# Sheet1.net
KiCad netlist of a schematic drawn in Altium Designer
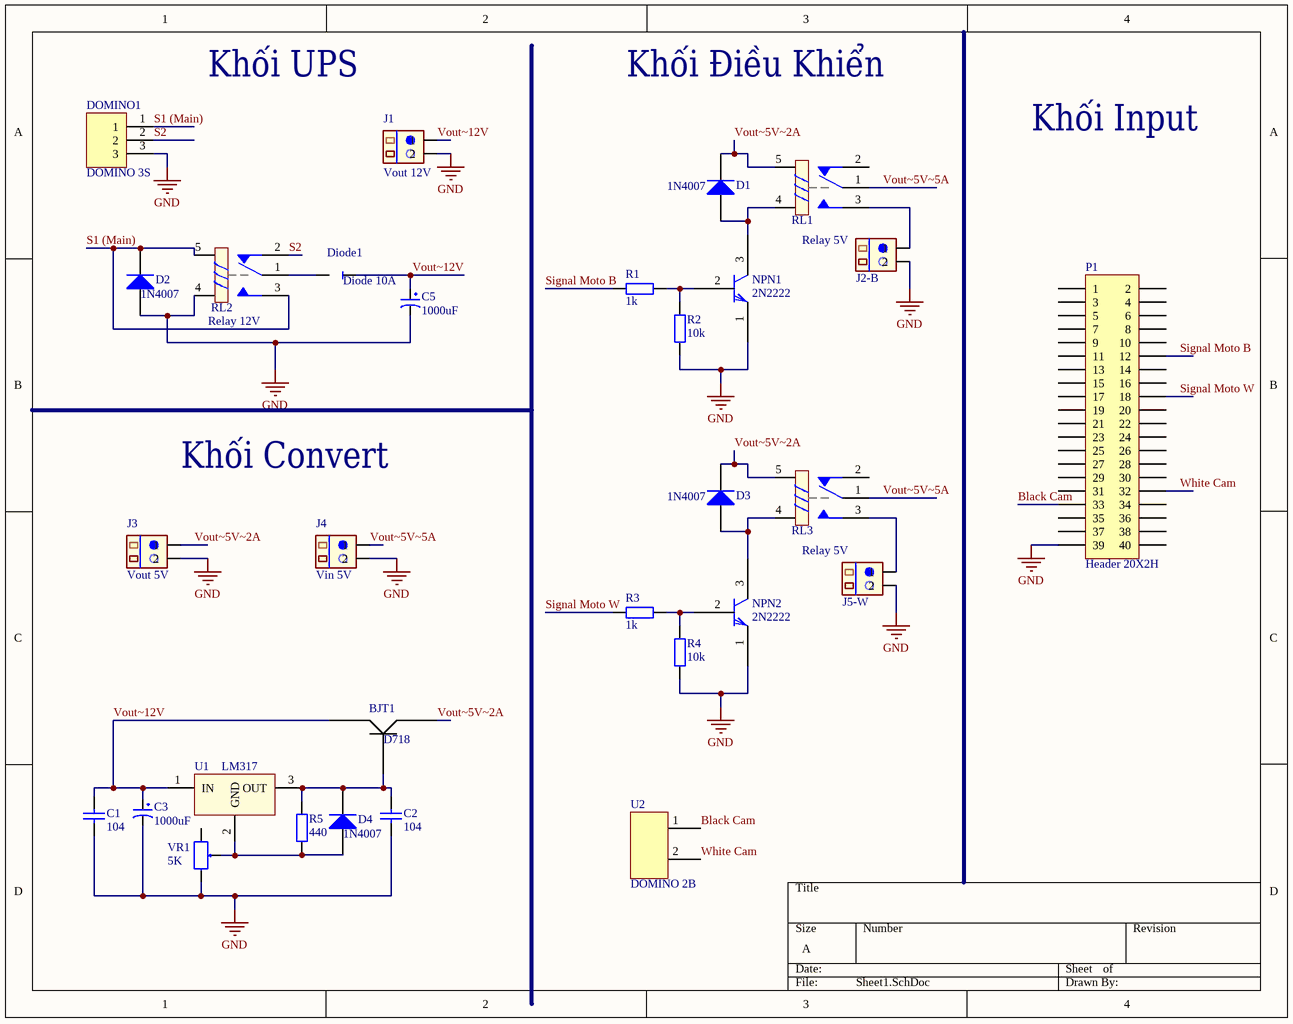
[diagram p0: Sheet1.SchDoc]

(export (version "E")
  (design (tool "Eeschema 10.0.6"))
  (components
    (comp (ref "BJT1") (value "D718") (footprint "2sb688") (libsource (lib "2sb688") (part "BJT 2sb688")))
    (comp (ref "C1")
      (value "104")
      (footprint "tu gom")
      (description "Cắm")
      (libsource (lib "THU VIEN SCH") (part "Tu gom 104 50V"))
    )
    (comp (ref "C2")
      (value "104")
      (footprint "tu gom")
      (description "Cắm")
      (libsource (lib "THU VIEN SCH") (part "Tu gom 104 50V"))
    )
    (comp (ref "C3")
      (value "1000uF")
      (footprint "tu hoa 13mm")
      (description "Cắm")
      (libsource (lib "THU VIEN SCH") (part "Tu Hoa 1000uF 25V 13x21"))
    )
    (comp (ref "C5")
      (value "1000uF")
      (footprint "tu hoa 13mm")
      (description "Cắm")
      (libsource (lib "THU VIEN SCH") (part "Tu Hoa 1000uF 25V 13x21"))
    )
    (comp (ref "D1")
      (value "1N4007")
      (footprint "DO-41")
      (description "1 Amp General Purpose Rectifier")
      (fields (field (name "PUBLISHER") "Altium Limited"))
      (libsource (lib "hphonglib") (part "Diode 1N4007"))
    )
    (comp (ref "D2")
      (value "1N4007")
      (footprint "DO-41")
      (description "1 Amp General Purpose Rectifier")
      (fields (field (name "PUBLISHER") "Altium Limited"))
      (libsource (lib "hphonglib") (part "Diode 1N4007"))
    )
    (comp (ref "D3")
      (value "1N4007")
      (footprint "DO-41")
      (description "1 Amp General Purpose Rectifier")
      (fields (field (name "PUBLISHER") "Altium Limited"))
      (libsource (lib "hphonglib") (part "Diode 1N4007"))
    )
    (comp (ref "D4")
      (value "1N4007")
      (footprint "DO-41")
      (description "1 Amp General Purpose Rectifier")
      (fields (field (name "PUBLISHER") "Altium Limited"))
      (libsource (lib "hphonglib") (part "Diode 1N4007"))
    )
    (comp (ref "Diode1")
      (value "Diode 10A")
      (footprint "Diode 6A10")
      (libsource (lib "Diode6A10") (part "Diode 6A10"))
    )
    (comp (ref "DOMINO1")
      (value "DOMINO 3S")
      (footprint "DOMINO 3S")
      (libsource (lib "hphonglib") (part "DOMINO 3S"))
    )
    (comp (ref "J1")
      (value "Vout 12V")
      (footprint "Domino 2M")
      (description "2 pins Domino Header")
      (fields (field (name "PUBLISHER") "Hoang Nguyen"))
      (libsource (lib "hphonglib") (part "CON.Domino2"))
    )
    (comp (ref "J2-B")
      (value "CON.Domino2")
      (footprint "Domino 2M")
      (description "2 pins Domino Header")
      (fields (field (name "PUBLISHER") "Hoang Nguyen"))
      (libsource (lib "hphonglib") (part "CON.Domino2"))
    )
    (comp (ref "J3")
      (value "Vout 5V")
      (footprint "Domino 2M")
      (description "Source DC 5V for Servo")
      (fields (field (name "PUBLISHER") "Hoang Nguyen"))
      (libsource (lib "hphonglib") (part "CON.Domino2"))
    )
    (comp (ref "J4")
      (value "Vin 5V")
      (footprint "Domino 2M")
      (description "Source DC from MODULE")
      (fields (field (name "PUBLISHER") "Hoang Nguyen"))
      (libsource (lib "hphonglib") (part "CON.Domino2"))
    )
    (comp (ref "J5-W")
      (value "CON.Domino2")
      (footprint "Domino 2M")
      (description "2 pins Domino Header")
      (fields (field (name "PUBLISHER") "Hoang Nguyen"))
      (libsource (lib "hphonglib") (part "CON.Domino2"))
    )
    (comp (ref "NPN1")
      (value "2N2222")
      (footprint "PCBComponent_1")
      (libsource (lib "2n2222") (part "Component_1"))
    )
    (comp (ref "NPN2")
      (value "2N2222")
      (footprint "PCBComponent_1")
      (libsource (lib "2n2222") (part "Component_1"))
    )
    (comp (ref "P1")
      (value "Header 20X2H")
      (footprint "HDR2X20H")
      (description "Header, 20-Pin, Dual row, Right Angle")
      (fields (field (name "PUBLISHER") "Altium Limited"))
      (libsource (lib "hphonglib") (part "Header 20X2H"))
    )
    (comp (ref "R1")
      (value "1k")
      (footprint "tro vach 1/4w")
      (description "Cắm")
      (libsource (lib "THU VIEN SCH") (part "Tro Vach 1/4W 5% 1k"))
    )
    (comp (ref "R2")
      (value "10k")
      (footprint "tro vach 1/4w")
      (description "Cắm")
      (libsource (lib "THU VIEN SCH") (part "Tro Vach 1/4W 1% 10k"))
    )
    (comp (ref "R3")
      (value "1k")
      (footprint "tro vach 1/4w")
      (description "Cắm")
      (libsource (lib "THU VIEN SCH") (part "Tro Vach 1/4W 5% 1k"))
    )
    (comp (ref "R4")
      (value "10k")
      (footprint "tro vach 1/4w")
      (description "Cắm")
      (libsource (lib "THU VIEN SCH") (part "Tro Vach 1/4W 1% 10k"))
    )
    (comp (ref "R5")
      (value "440")
      (footprint "tro vach 1/4w")
      (description "Cắm")
      (libsource (lib "THU VIEN SCH") (part "Tro Vach 1/4W 5% 1k"))
    )
    (comp (ref "RL1")
      (value "Relay 5V")
      (footprint "PCBComponent_1 - duplicate")
      (description "Cắm")
      (libsource (lib "THU VIEN SCH") (part "Relay 10A"))
    )
    (comp (ref "RL2")
      (value "Relay 12V")
      (footprint "RELAY5PIN-10A")
      (description "Cắm")
      (libsource (lib "THU VIEN SCH") (part "Relay 10A"))
    )
    (comp (ref "RL3")
      (value "Relay 5V")
      (footprint "PCBComponent_1 - duplicate")
      (description "Cắm")
      (libsource (lib "THU VIEN SCH") (part "Relay 10A"))
    )
    (comp (ref "U1")
      (value "LM317")
      (footprint "QTO-220H3")
      (description "LM78xx, on ap +")
      (libsource (lib "sch") (part "78xx"))
    )
    (comp (ref "U2")
      (value "DOMINO 2B")
      (footprint "DOMINO 2B")
      (libsource (lib "hphonglib") (part "DOMINO 2B"))
    )
    (comp (ref "VR1")
      (value "5K")
      (footprint "RVAR10K")
      (description "Cắm")
      (libsource (lib "THU VIEN SCH") (part "Bien Tro Tinh Chinh 1K"))
    )
  )
  (nets
    (net (code "1") (name "/Black Cam") (class "Default")
      (node (ref "P1") (pin "33") (pinfunction "33_33") (pintype "passive"))
      (node (ref "U2") (pin "1") (pintype "passive"))
    )
    (net (code "2") (name "/S1 (Main)") (class "Default")
      (node (ref "D2") (pin "2") (pinfunction "K_2") (pintype "passive"))
      (node (ref "DOMINO1") (pin "1") (pinfunction "1_1") (pintype "passive"))
      (node (ref "RL2") (pin "3") (pinfunction "3_3") (pintype "passive"))
      (node (ref "RL2") (pin "5") (pinfunction "5_5") (pintype "passive"))
    )
    (net (code "3") (name "/S2") (class "Default")
      (node (ref "DOMINO1") (pin "2") (pinfunction "2_2") (pintype "passive"))
      (node (ref "RL2") (pin "2") (pinfunction "2_2") (pintype "passive"))
    )
    (net (code "4") (name "/Signal Moto B") (class "Default")
      (node (ref "P1") (pin "12") (pinfunction "12_12") (pintype "passive"))
      (node (ref "R1") (pin "1") (pinfunction "1_1") (pintype "passive"))
    )
    (net (code "5") (name "/Signal Moto W") (class "Default")
      (node (ref "P1") (pin "18") (pinfunction "18_18") (pintype "passive"))
      (node (ref "R3") (pin "1") (pinfunction "1_1") (pintype "passive"))
    )
    (net (code "6") (name "/Vout~5V~2A") (class "Default")
      (node (ref "BJT1") (pin "3") (pinfunction "3_3") (pintype "passive"))
      (node (ref "D1") (pin "2") (pinfunction "K_2") (pintype "passive"))
      (node (ref "D3") (pin "2") (pinfunction "K_2") (pintype "passive"))
      (node (ref "J3") (pin "1") (pinfunction "1_1") (pintype "passive"))
      (node (ref "RL1") (pin "5") (pinfunction "5_5") (pintype "passive"))
      (node (ref "RL3") (pin "5") (pinfunction "5_5") (pintype "passive"))
    )
    (net (code "7") (name "/Vout~5V~5A") (class "Default")
      (node (ref "J4") (pin "1") (pinfunction "1_1") (pintype "passive"))
      (node (ref "RL1") (pin "1") (pinfunction "1_1") (pintype "passive"))
      (node (ref "RL3") (pin "1") (pinfunction "1_1") (pintype "passive"))
    )
    (net (code "8") (name "/Vout~12V") (class "Default")
      (node (ref "BJT1") (pin "2") (pinfunction "2_2") (pintype "passive"))
      (node (ref "C1") (pin "1") (pinfunction "1_1") (pintype "passive"))
      (node (ref "C3") (pin "1") (pinfunction "1_1") (pintype "passive"))
      (node (ref "C5") (pin "1") (pinfunction "1_1") (pintype "passive"))
      (node (ref "Diode1") (pin "2") (pinfunction "2_2") (pintype "passive"))
      (node (ref "J1") (pin "1") (pinfunction "1_1") (pintype "passive"))
      (node (ref "U1") (pin "1") (pinfunction "IN_1") (pintype "passive"))
    )
    (net (code "9") (name "/White Cam") (class "Default")
      (node (ref "P1") (pin "32") (pinfunction "32_32") (pintype "passive"))
      (node (ref "U2") (pin "2") (pintype "passive"))
    )
    (net (code "10") (name "GND") (class "Default")
      (node (ref "C1") (pin "2") (pinfunction "2_2") (pintype "passive"))
      (node (ref "C2") (pin "2") (pinfunction "2_2") (pintype "passive"))
      (node (ref "C3") (pin "2") (pinfunction "2_2") (pintype "passive"))
      (node (ref "C5") (pin "2") (pinfunction "2_2") (pintype "passive"))
      (node (ref "D2") (pin "1") (pinfunction "A_1") (pintype "passive"))
      (node (ref "DOMINO1") (pin "3") (pinfunction "3_3") (pintype "passive"))
      (node (ref "J1") (pin "2") (pinfunction "2_2") (pintype "passive"))
      (node (ref "J2-B") (pin "2") (pinfunction "2_2") (pintype "passive"))
      (node (ref "J3") (pin "2") (pinfunction "2_2") (pintype "passive"))
      (node (ref "J4") (pin "2") (pinfunction "2_2") (pintype "passive"))
      (node (ref "J5-W") (pin "2") (pinfunction "2_2") (pintype "passive"))
      (node (ref "NPN1") (pin "1") (pinfunction "1_1") (pintype "passive"))
      (node (ref "NPN2") (pin "1") (pinfunction "1_1") (pintype "passive"))
      (node (ref "P1") (pin "39") (pinfunction "39_39") (pintype "passive"))
      (node (ref "R2") (pin "1") (pinfunction "1_1") (pintype "passive"))
      (node (ref "R4") (pin "1") (pinfunction "1_1") (pintype "passive"))
      (node (ref "RL2") (pin "4") (pinfunction "4_4") (pintype "passive"))
      (node (ref "VR1") (pin "3") (pinfunction "3_3") (pintype "passive"))
    )
    (net (code "11") (name "Net-(D1-A)") (class "Default")
      (node (ref "D1") (pin "1") (pinfunction "A_1") (pintype "passive"))
      (node (ref "NPN1") (pin "3") (pinfunction "3_3") (pintype "passive"))
      (node (ref "RL1") (pin "4") (pinfunction "4_4") (pintype "passive"))
    )
    (net (code "12") (name "Net-(D3-A)") (class "Default")
      (node (ref "D3") (pin "1") (pinfunction "A_1") (pintype "passive"))
      (node (ref "NPN2") (pin "3") (pinfunction "3_3") (pintype "passive"))
      (node (ref "RL3") (pin "4") (pinfunction "4_4") (pintype "passive"))
    )
    (net (code "13") (name "Net-(D4-A)") (class "Default")
      (node (ref "D4") (pin "1") (pinfunction "A_1") (pintype "passive"))
      (node (ref "R5") (pin "1") (pinfunction "1_1") (pintype "passive"))
      (node (ref "U1") (pin "2") (pinfunction "GND_2") (pintype "passive"))
      (node (ref "VR1") (pin "2") (pinfunction "2_2") (pintype "passive"))
    )
    (net (code "14") (name "Net-(D4-K)") (class "Default")
      (node (ref "BJT1") (pin "1") (pinfunction "1_1") (pintype "passive"))
      (node (ref "C2") (pin "1") (pinfunction "1_1") (pintype "passive"))
      (node (ref "D4") (pin "2") (pinfunction "K_2") (pintype "passive"))
      (node (ref "R5") (pin "2") (pinfunction "2_2") (pintype "passive"))
      (node (ref "U1") (pin "3") (pinfunction "OUT_3") (pintype "passive"))
    )
    (net (code "15") (name "Net-(Diode1-Pad1)") (class "Default")
      (node (ref "Diode1") (pin "1") (pinfunction "1_1") (pintype "passive"))
      (node (ref "RL2") (pin "1") (pinfunction "1_1") (pintype "passive"))
    )
    (net (code "16") (name "Net-(J2-B-Pad1)") (class "Default")
      (node (ref "J2-B") (pin "1") (pinfunction "1_1") (pintype "passive"))
      (node (ref "RL1") (pin "3") (pinfunction "3_3") (pintype "passive"))
    )
    (net (code "17") (name "Net-(J5-W-Pad1)") (class "Default")
      (node (ref "J5-W") (pin "1") (pinfunction "1_1") (pintype "passive"))
      (node (ref "RL3") (pin "3") (pinfunction "3_3") (pintype "passive"))
    )
    (net (code "18") (name "Net-(NPN1-Pad2)") (class "Default")
      (node (ref "NPN1") (pin "2") (pinfunction "2_2") (pintype "passive"))
      (node (ref "R1") (pin "2") (pinfunction "2_2") (pintype "passive"))
      (node (ref "R2") (pin "2") (pinfunction "2_2") (pintype "passive"))
    )
    (net (code "19") (name "Net-(NPN2-Pad2)") (class "Default")
      (node (ref "NPN2") (pin "2") (pinfunction "2_2") (pintype "passive"))
      (node (ref "R3") (pin "2") (pinfunction "2_2") (pintype "passive"))
      (node (ref "R4") (pin "2") (pinfunction "2_2") (pintype "passive"))
    )
    (net (code "20") (name "unconnected-(P1-Pad1)") (class "Default")
      (node (ref "P1") (pin "1") (pinfunction "1_1") (pintype "passive"))
    )
    (net (code "21") (name "unconnected-(P1-Pad2)") (class "Default")
      (node (ref "P1") (pin "2") (pinfunction "2_2") (pintype "passive"))
    )
    (net (code "22") (name "unconnected-(P1-Pad3)") (class "Default")
      (node (ref "P1") (pin "3") (pinfunction "3_3") (pintype "passive"))
    )
    (net (code "23") (name "unconnected-(P1-Pad4)") (class "Default")
      (node (ref "P1") (pin "4") (pinfunction "4_4") (pintype "passive"))
    )
    (net (code "24") (name "unconnected-(P1-Pad5)") (class "Default")
      (node (ref "P1") (pin "5") (pinfunction "5_5") (pintype "passive"))
    )
    (net (code "25") (name "unconnected-(P1-Pad6)") (class "Default")
      (node (ref "P1") (pin "6") (pinfunction "6_6") (pintype "passive"))
    )
    (net (code "26") (name "unconnected-(P1-Pad7)") (class "Default")
      (node (ref "P1") (pin "7") (pinfunction "7_7") (pintype "passive"))
    )
    (net (code "27") (name "unconnected-(P1-Pad8)") (class "Default")
      (node (ref "P1") (pin "8") (pinfunction "8_8") (pintype "passive"))
    )
    (net (code "28") (name "unconnected-(P1-Pad9)") (class "Default")
      (node (ref "P1") (pin "9") (pinfunction "9_9") (pintype "passive"))
    )
    (net (code "29") (name "unconnected-(P1-Pad10)") (class "Default")
      (node (ref "P1") (pin "10") (pinfunction "10_10") (pintype "passive"))
    )
    (net (code "30") (name "unconnected-(P1-Pad11)") (class "Default")
      (node (ref "P1") (pin "11") (pinfunction "11_11") (pintype "passive"))
    )
    (net (code "31") (name "unconnected-(P1-Pad13)") (class "Default")
      (node (ref "P1") (pin "13") (pinfunction "13_13") (pintype "passive"))
    )
    (net (code "32") (name "unconnected-(P1-Pad14)") (class "Default")
      (node (ref "P1") (pin "14") (pinfunction "14_14") (pintype "passive"))
    )
    (net (code "33") (name "unconnected-(P1-Pad15)") (class "Default")
      (node (ref "P1") (pin "15") (pinfunction "15_15") (pintype "passive"))
    )
    (net (code "34") (name "unconnected-(P1-Pad16)") (class "Default")
      (node (ref "P1") (pin "16") (pinfunction "16_16") (pintype "passive"))
    )
    (net (code "35") (name "unconnected-(P1-Pad17)") (class "Default")
      (node (ref "P1") (pin "17") (pinfunction "17_17") (pintype "passive"))
    )
    (net (code "36") (name "unconnected-(P1-Pad19)") (class "Default")
      (node (ref "P1") (pin "19") (pinfunction "19_19") (pintype "passive"))
    )
    (net (code "37") (name "unconnected-(P1-Pad20)") (class "Default")
      (node (ref "P1") (pin "20") (pinfunction "20_20") (pintype "passive"))
    )
    (net (code "38") (name "unconnected-(P1-Pad21)") (class "Default")
      (node (ref "P1") (pin "21") (pinfunction "21_21") (pintype "passive"))
    )
    (net (code "39") (name "unconnected-(P1-Pad22)") (class "Default")
      (node (ref "P1") (pin "22") (pinfunction "22_22") (pintype "passive"))
    )
    (net (code "40") (name "unconnected-(P1-Pad23)") (class "Default")
      (node (ref "P1") (pin "23") (pinfunction "23_23") (pintype "passive"))
    )
    (net (code "41") (name "unconnected-(P1-Pad24)") (class "Default")
      (node (ref "P1") (pin "24") (pinfunction "24_24") (pintype "passive"))
    )
    (net (code "42") (name "unconnected-(P1-Pad25)") (class "Default")
      (node (ref "P1") (pin "25") (pinfunction "25_25") (pintype "passive"))
    )
    (net (code "43") (name "unconnected-(P1-Pad26)") (class "Default")
      (node (ref "P1") (pin "26") (pinfunction "26_26") (pintype "passive"))
    )
    (net (code "44") (name "unconnected-(P1-Pad27)") (class "Default")
      (node (ref "P1") (pin "27") (pinfunction "27_27") (pintype "passive"))
    )
    (net (code "45") (name "unconnected-(P1-Pad28)") (class "Default")
      (node (ref "P1") (pin "28") (pinfunction "28_28") (pintype "passive"))
    )
    (net (code "46") (name "unconnected-(P1-Pad29)") (class "Default")
      (node (ref "P1") (pin "29") (pinfunction "29_29") (pintype "passive"))
    )
    (net (code "47") (name "unconnected-(P1-Pad30)") (class "Default")
      (node (ref "P1") (pin "30") (pinfunction "30_30") (pintype "passive"))
    )
    (net (code "48") (name "unconnected-(P1-Pad31)") (class "Default")
      (node (ref "P1") (pin "31") (pinfunction "31_31") (pintype "passive"))
    )
    (net (code "49") (name "unconnected-(P1-Pad34)") (class "Default")
      (node (ref "P1") (pin "34") (pinfunction "34_34") (pintype "passive"))
    )
    (net (code "50") (name "unconnected-(P1-Pad35)") (class "Default")
      (node (ref "P1") (pin "35") (pinfunction "35_35") (pintype "passive"))
    )
    (net (code "51") (name "unconnected-(P1-Pad36)") (class "Default")
      (node (ref "P1") (pin "36") (pinfunction "36_36") (pintype "passive"))
    )
    (net (code "52") (name "unconnected-(P1-Pad37)") (class "Default")
      (node (ref "P1") (pin "37") (pinfunction "37_37") (pintype "passive"))
    )
    (net (code "53") (name "unconnected-(P1-Pad38)") (class "Default")
      (node (ref "P1") (pin "38") (pinfunction "38_38") (pintype "passive"))
    )
    (net (code "54") (name "unconnected-(P1-Pad40)") (class "Default")
      (node (ref "P1") (pin "40") (pinfunction "40_40") (pintype "passive"))
    )
    (net (code "55") (name "unconnected-(RL1-Pad2)") (class "Default")
      (node (ref "RL1") (pin "2") (pinfunction "2_2") (pintype "passive"))
    )
    (net (code "56") (name "unconnected-(RL3-Pad2)") (class "Default")
      (node (ref "RL3") (pin "2") (pinfunction "2_2") (pintype "passive"))
    )
    (net (code "57") (name "unconnected-(VR1-Pad1)") (class "Default")
      (node (ref "VR1") (pin "1") (pinfunction "1_1") (pintype "passive"))
    )
  )
)
